# power.net
KiCad netlist of a schematic drawn in Altium Designer
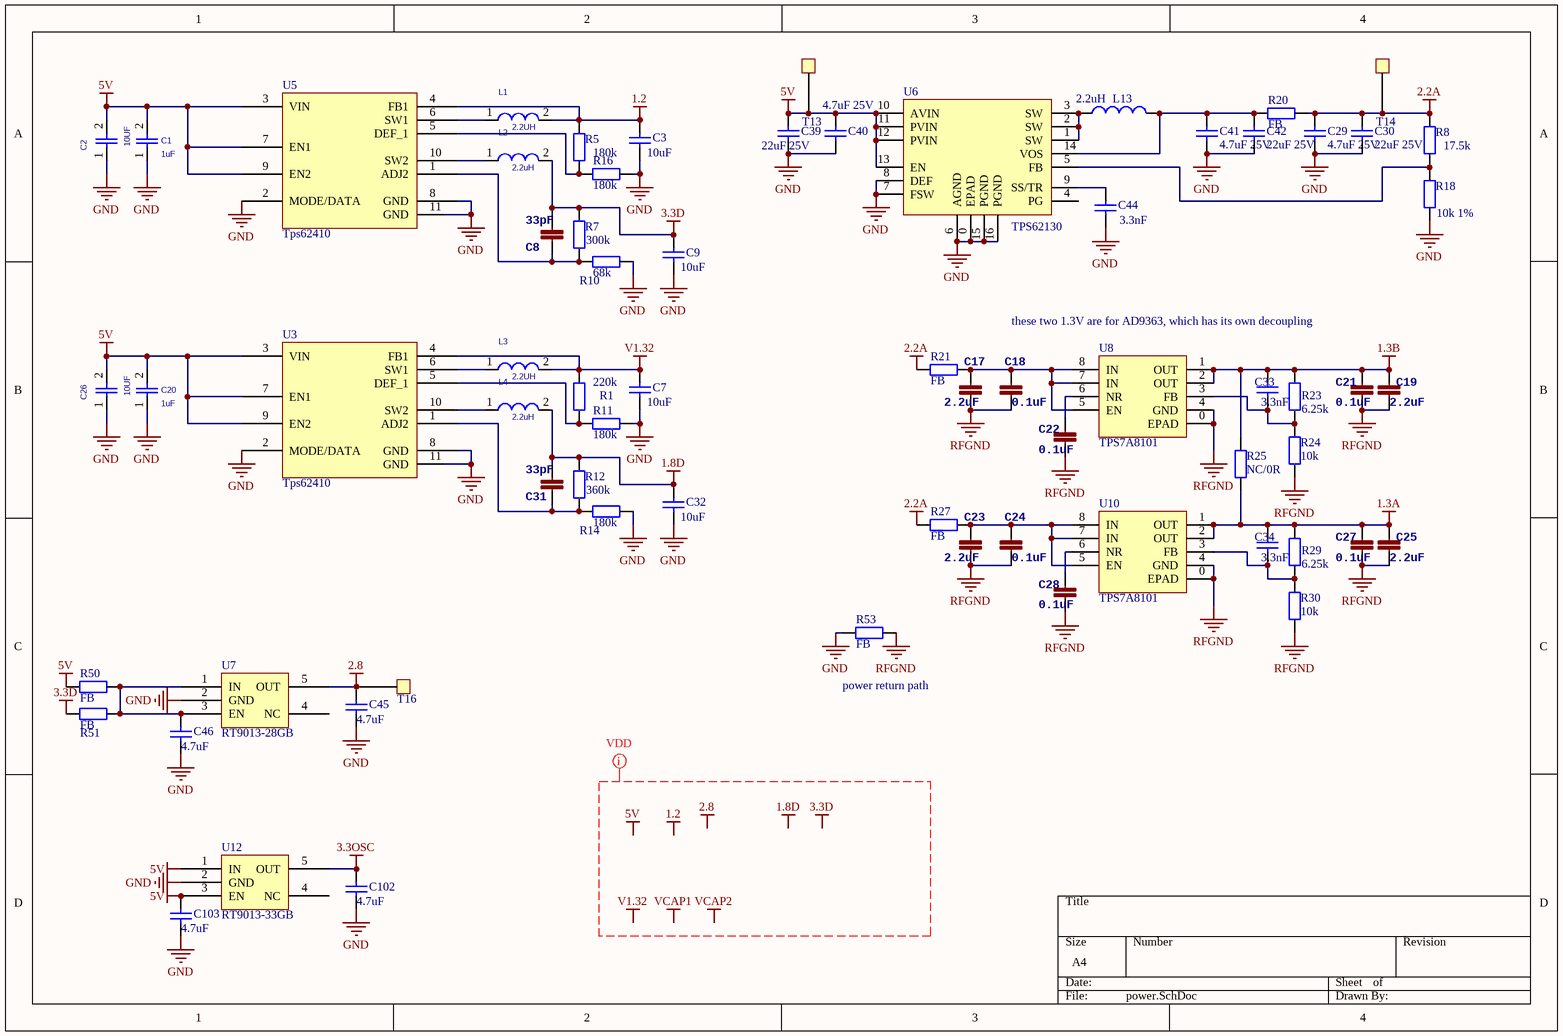
[diagram p0: power.SchDoc]

(export (version "E")
  (design (tool "Eeschema 10.0.6"))
  (components
    (comp (ref "C1") (value "1uF") (footprint "0603") (libsource (lib "*") (part "CAP/0402")))
    (comp (ref "C2") (value "10UF") (footprint "0805") (libsource (lib "*") (part "CAP/0402")))
    (comp (ref "C3")
      (value "10uF")
      (footprint "0805")
      (description "Capacitor")
      (fields (field (name "PUBLISHER") "Altium Limited"))
      (libsource (lib "RTC6705") (part "Cap"))
    )
    (comp (ref "C7")
      (value "10uF")
      (footprint "0805")
      (description "Capacitor")
      (fields (field (name "PUBLISHER") "Altium Limited"))
      (libsource (lib "RTC6705") (part "Cap"))
    )
    (comp (ref "C8")
      (value "33pF")
      (footprint "0402")
      (description "<b>Capacitor</b>\nStandard 0603 ceramic capacitor, and 0.1\" leaded capacitor.")
      (fields (field (name "PARTNO") "CC0402ZRY5V7BB104"))
      (libsource (lib "") (part "CAP0402-CAP_1"))
    )
    (comp (ref "C9")
      (value "10uF")
      (footprint "0805")
      (description "Capacitor")
      (fields (field (name "PUBLISHER") "Altium Limited"))
      (libsource (lib "RTC6705") (part "Cap"))
    )
    (comp (ref "C17")
      (value "2.2uF")
      (footprint "0603")
      (description "<b>Capacitor</b>\nStandard 0603 ceramic capacitor, and 0.1\" leaded capacitor.")
      (fields (field (name "PARTNO") "CC0402ZRY5V7BB104"))
      (libsource (lib "pixhawk2") (part "CAP0402-CAP"))
    )
    (comp (ref "C18")
      (value "0.1uF")
      (footprint "0402")
      (description "<b>Capacitor</b>\nStandard 0603 ceramic capacitor, and 0.1\" leaded capacitor.")
      (fields (field (name "PARTNO") "CC0402ZRY5V7BB104"))
      (libsource (lib "*") (part "CAP0402-CAP"))
    )
    (comp (ref "C19")
      (value "2.2uF")
      (footprint "0603")
      (description "<b>Capacitor</b>\nStandard 0603 ceramic capacitor, and 0.1\" leaded capacitor.")
      (fields (field (name "PARTNO") "CC0402ZRY5V7BB104"))
      (libsource (lib "pixhawk2") (part "CAP0402-CAP"))
    )
    (comp (ref "C20") (value "1uF") (footprint "0603") (libsource (lib "*") (part "CAP/0402")))
    (comp (ref "C21")
      (value "0.1uF")
      (footprint "0603")
      (description "<b>Capacitor</b>\nStandard 0603 ceramic capacitor, and 0.1\" leaded capacitor.")
      (fields (field (name "PARTNO") "CC0402ZRY5V7BB104"))
      (libsource (lib "*") (part "CAP0402-CAP"))
    )
    (comp (ref "C22")
      (value "0.1uF")
      (footprint "0402")
      (description "<b>Capacitor</b>\nStandard 0603 ceramic capacitor, and 0.1\" leaded capacitor.")
      (fields (field (name "PARTNO") "CC0402ZRY5V7BB104"))
      (libsource (lib "*") (part "CAP0402-CAP"))
    )
    (comp (ref "C23")
      (value "2.2uF")
      (footprint "0603")
      (description "<b>Capacitor</b>\nStandard 0603 ceramic capacitor, and 0.1\" leaded capacitor.")
      (fields (field (name "PARTNO") "CC0402ZRY5V7BB104"))
      (libsource (lib "pixhawk2") (part "CAP0402-CAP"))
    )
    (comp (ref "C24")
      (value "0.1uF")
      (footprint "0402")
      (description "<b>Capacitor</b>\nStandard 0603 ceramic capacitor, and 0.1\" leaded capacitor.")
      (fields (field (name "PARTNO") "CC0402ZRY5V7BB104"))
      (libsource (lib "*") (part "CAP0402-CAP"))
    )
    (comp (ref "C25")
      (value "2.2uF")
      (footprint "0603")
      (description "<b>Capacitor</b>\nStandard 0603 ceramic capacitor, and 0.1\" leaded capacitor.")
      (fields (field (name "PARTNO") "CC0402ZRY5V7BB104"))
      (libsource (lib "pixhawk2") (part "CAP0402-CAP"))
    )
    (comp (ref "C26") (value "10UF") (footprint "0805") (libsource (lib "*") (part "CAP/0402")))
    (comp (ref "C27")
      (value "0.1uF")
      (footprint "0603")
      (description "<b>Capacitor</b>\nStandard 0603 ceramic capacitor, and 0.1\" leaded capacitor.")
      (fields (field (name "PARTNO") "CC0402ZRY5V7BB104"))
      (libsource (lib "*") (part "CAP0402-CAP"))
    )
    (comp (ref "C28")
      (value "0.1uF")
      (footprint "0402")
      (description "<b>Capacitor</b>\nStandard 0603 ceramic capacitor, and 0.1\" leaded capacitor.")
      (fields (field (name "PARTNO") "CC0402ZRY5V7BB104"))
      (libsource (lib "*") (part "CAP0402-CAP"))
    )
    (comp (ref "C29")
      (value "4.7uF 25V")
      (footprint "0603")
      (description "Capacitor")
      (fields (field (name "Comment") "Cap") (field (name "PUBLISHER") "Altium Limited"))
      (libsource (lib "RTC6705") (part "Cap"))
    )
    (comp (ref "C30")
      (value "22uF 25V")
      (footprint "0805")
      (description "Capacitor")
      (fields (field (name "Comment") "Cap") (field (name "PUBLISHER") "Altium Limited"))
      (libsource (lib "RTC6705") (part "Cap"))
    )
    (comp (ref "C31")
      (value "33pF")
      (footprint "0402")
      (description "<b>Capacitor</b>\nStandard 0603 ceramic capacitor, and 0.1\" leaded capacitor.")
      (fields (field (name "PARTNO") "CC0402ZRY5V7BB104"))
      (libsource (lib "") (part "CAP0402-CAP_1"))
    )
    (comp (ref "C32")
      (value "10uF")
      (footprint "0805")
      (description "Capacitor")
      (fields (field (name "PUBLISHER") "Altium Limited"))
      (libsource (lib "RTC6705") (part "Cap"))
    )
    (comp (ref "C33")
      (value "3.3nF")
      (footprint "0402")
      (description "Capacitor")
      (fields (field (name "PUBLISHER") "Altium Limited"))
      (libsource (lib "RTC6705") (part "Cap"))
    )
    (comp (ref "C34")
      (value "3.3nF")
      (footprint "0402")
      (description "Capacitor")
      (fields (field (name "PUBLISHER") "Altium Limited"))
      (libsource (lib "RTC6705") (part "Cap"))
    )
    (comp (ref "C39")
      (value "22uF 25V")
      (footprint "0805")
      (description "Capacitor")
      (fields (field (name "Comment") "Cap") (field (name "PUBLISHER") "Altium Limited"))
      (libsource (lib "RTC6705") (part "Cap"))
    )
    (comp (ref "C40")
      (value "4.7uF 25V")
      (footprint "0603")
      (description "Capacitor")
      (fields (field (name "Comment") "Cap") (field (name "PUBLISHER") "Altium Limited"))
      (libsource (lib "RTC6705") (part "Cap"))
    )
    (comp (ref "C41")
      (value "4.7uF 25V")
      (footprint "0603")
      (description "Capacitor")
      (fields (field (name "Comment") "Cap") (field (name "PUBLISHER") "Altium Limited"))
      (libsource (lib "RTC6705") (part "Cap"))
    )
    (comp (ref "C42")
      (value "22uF 25V")
      (footprint "0805")
      (description "Capacitor")
      (fields (field (name "Comment") "Cap") (field (name "PUBLISHER") "Altium Limited"))
      (libsource (lib "RTC6705") (part "Cap"))
    )
    (comp (ref "C44")
      (value "3.3nF")
      (footprint "0402")
      (description "Capacitor")
      (fields (field (name "PUBLISHER") "Altium Limited"))
      (libsource (lib "RTC6705") (part "Cap"))
    )
    (comp (ref "C45")
      (value "4.7uF")
      (footprint "0603")
      (description "Capacitor")
      (fields (field (name "PUBLISHER") "Altium Limited"))
      (libsource (lib "RTC6705") (part "Cap"))
    )
    (comp (ref "C46")
      (value "4.7uF")
      (footprint "0603")
      (description "Capacitor")
      (fields (field (name "PUBLISHER") "Altium Limited"))
      (libsource (lib "RTC6705") (part "Cap"))
    )
    (comp (ref "C102")
      (value "4.7uF")
      (footprint "0603")
      (description "Capacitor")
      (fields (field (name "PUBLISHER") "Altium Limited"))
      (libsource (lib "RTC6705") (part "Cap"))
    )
    (comp (ref "C103")
      (value "4.7uF")
      (footprint "0603")
      (description "Capacitor")
      (fields (field (name "PUBLISHER") "Altium Limited"))
      (libsource (lib "RTC6705") (part "Cap"))
    )
    (comp (ref "L1") (value "2.2UH") (footprint "0806") (libsource (lib "*") (part "L/2.5*2.0")))
    (comp (ref "L2") (value "2.2uH") (footprint "0806") (libsource (lib "*") (part "L/2.5*2.0")))
    (comp (ref "L3") (value "2.2UH") (footprint "0806") (libsource (lib "*") (part "L/2.5*2.0")))
    (comp (ref "L4") (value "2.2uH") (footprint "0806") (libsource (lib "*") (part "L/2.5*2.0")))
    (comp (ref "L13")
      (value "2.2uH")
      (footprint "L3015")
      (description "Inductor")
      (fields (field (name "PUBLISHER") "Altium Limited"))
      (libsource (lib "Miscellaneous Devices") (part "Inductor"))
    )
    (comp (ref "R1")
      (value "220k")
      (footprint "0402")
      (description "Resistor")
      (fields (field (name "PUBLISHER") "Altium Limited"))
      (libsource (lib "RTC6705") (part "Res2"))
    )
    (comp (ref "R5")
      (value "180k")
      (footprint "0402")
      (description "Resistor")
      (fields (field (name "PUBLISHER") "Altium Limited"))
      (libsource (lib "RTC6705") (part "Res2"))
    )
    (comp (ref "R7")
      (value "300k")
      (footprint "0402")
      (description "Resistor")
      (fields (field (name "PUBLISHER") "Altium Limited"))
      (libsource (lib "RTC6705") (part "Res2"))
    )
    (comp (ref "R8")
      (value "17.5k")
      (footprint "0402")
      (description "Resistor")
      (fields (field (name "PUBLISHER") "Altium Limited"))
      (libsource (lib "RTC6705") (part "Res2"))
    )
    (comp (ref "R10")
      (value "68k")
      (footprint "0402")
      (description "Resistor")
      (fields (field (name "PUBLISHER") "Altium Limited"))
      (libsource (lib "") (part "Res2_1"))
    )
    (comp (ref "R11")
      (value "180k")
      (footprint "0402")
      (description "Resistor")
      (fields (field (name "PUBLISHER") "Altium Limited"))
      (libsource (lib "") (part "Res2_1"))
    )
    (comp (ref "R12")
      (value "360k")
      (footprint "0402")
      (description "Resistor")
      (fields (field (name "PUBLISHER") "Altium Limited"))
      (libsource (lib "RTC6705") (part "Res2"))
    )
    (comp (ref "R14")
      (value "180k")
      (footprint "0402")
      (description "Resistor")
      (fields (field (name "PUBLISHER") "Altium Limited"))
      (libsource (lib "") (part "Res2_1"))
    )
    (comp (ref "R16")
      (value "180k")
      (footprint "0402")
      (description "Resistor")
      (fields (field (name "PUBLISHER") "Altium Limited"))
      (libsource (lib "") (part "Res2_1"))
    )
    (comp (ref "R18")
      (value "10k 1%")
      (footprint "0402")
      (description "Resistor")
      (fields (field (name "PUBLISHER") "Altium Limited"))
      (libsource (lib "RTC6705") (part "Res2"))
    )
    (comp (ref "R20")
      (value "FB")
      (footprint "0603")
      (description "Resistor")
      (fields (field (name "PUBLISHER") "Altium Limited"))
      (libsource (lib "Miscellaneous Devices") (part "Res2"))
    )
    (comp (ref "R21")
      (value "FB")
      (footprint "0603")
      (description "Resistor")
      (fields (field (name "PUBLISHER") "Altium Limited"))
      (libsource (lib "Miscellaneous Devices") (part "Res2"))
    )
    (comp (ref "R23")
      (value "6.25k")
      (footprint "0402")
      (description "Resistor")
      (fields (field (name "PUBLISHER") "Altium Limited"))
      (libsource (lib "") (part "Res2_2"))
    )
    (comp (ref "R24")
      (value "10k")
      (footprint "0402")
      (description "Resistor")
      (fields (field (name "PUBLISHER") "Altium Limited"))
      (libsource (lib "") (part "Res2_2"))
    )
    (comp (ref "R25")
      (value "NC/0R")
      (footprint "0603")
      (description "Resistor")
      (fields (field (name "PUBLISHER") "Altium Limited"))
      (libsource (lib "") (part "Res2_2"))
    )
    (comp (ref "R27")
      (value "FB")
      (footprint "0603")
      (description "Resistor")
      (fields (field (name "PUBLISHER") "Altium Limited"))
      (libsource (lib "Miscellaneous Devices") (part "Res2"))
    )
    (comp (ref "R29")
      (value "6.25k")
      (footprint "0402")
      (description "Resistor")
      (fields (field (name "PUBLISHER") "Altium Limited"))
      (libsource (lib "") (part "Res2_2"))
    )
    (comp (ref "R30")
      (value "10k")
      (footprint "0402")
      (description "Resistor")
      (fields (field (name "PUBLISHER") "Altium Limited"))
      (libsource (lib "") (part "Res2_2"))
    )
    (comp (ref "R50")
      (value "FB")
      (footprint "0603")
      (description "Resistor")
      (fields (field (name "PUBLISHER") "Altium Limited"))
      (libsource (lib "") (part "Res2_1"))
    )
    (comp (ref "R51")
      (value "FB")
      (footprint "0603")
      (description "Resistor")
      (fields (field (name "PUBLISHER") "Altium Limited"))
      (libsource (lib "") (part "Res2_1"))
    )
    (comp (ref "R53")
      (value "FB")
      (footprint "0603")
      (description "Resistor")
      (fields (field (name "PUBLISHER") "Altium Limited"))
      (libsource (lib "Miscellaneous Devices") (part "Res2"))
    )
    (comp (ref "T13") (value "TestPad") (footprint "TestPad - 1mm") (libsource (lib "") (part "TestPad_1")))
    (comp (ref "T14") (value "TestPad") (footprint "TestPad - 1mm") (libsource (lib "") (part "TestPad_1")))
    (comp (ref "T16") (value "TestPad") (footprint "TestPad - 1mm") (libsource (lib "sch") (part "TestPad")))
    (comp (ref "U3") (value "Tps62410") (footprint "DFN-10P-3X3") (libsource (lib "Euler") (part "Tps62410")))
    (comp (ref "U5") (value "Tps62410") (footprint "DFN-10P-3X3") (libsource (lib "Euler") (part "Tps62410")))
    (comp (ref "U6") (value "TPS62130") (footprint "TPS62130") (libsource (lib "sch") (part "TPS62130")))
    (comp (ref "U7") (value "RT9013-28GB") (footprint "SOT23-5") (libsource (lib "RTC6705") (part "LP5907")))
    (comp (ref "U8") (value "TPS7A8101") (footprint "TPS7A8101") (libsource (lib "F4SDR") (part "TPS7A8101")))
    (comp (ref "U10")
      (value "TPS7A8101")
      (footprint "TPS7A8101")
      (libsource (lib "F4SDR") (part "TPS7A8101"))
    )
    (comp (ref "U12") (value "RT9013-33GB") (footprint "SOT23-5") (libsource (lib "RTC6705") (part "LP5907")))
  )
  (nets
    (net (code "1") (name "1.2") (class "Default")
      (node (ref "C3") (pin "2") (pinfunction "2_2") (pintype "passive"))
      (node (ref "L1") (pin "2") (pinfunction "2_2") (pintype "passive"))
      (node (ref "R5") (pin "1") (pinfunction "1_1") (pintype "passive"))
      (node (ref "U5") (pin "4") (pinfunction "FB1_4") (pintype "passive"))
    )
    (net (code "2") (name "1.3A") (class "Default")
      (node (ref "C25") (pin "2") (pinfunction "2_2") (pintype "passive"))
      (node (ref "C27") (pin "2") (pinfunction "2_2") (pintype "passive"))
      (node (ref "C34") (pin "1") (pinfunction "1_1") (pintype "passive"))
      (node (ref "R25") (pin "2") (pinfunction "2_2") (pintype "passive"))
      (node (ref "R29") (pin "1") (pinfunction "1_1") (pintype "passive"))
      (node (ref "U10") (pin "1") (pinfunction "OUT_1") (pintype "passive"))
      (node (ref "U10") (pin "2") (pinfunction "OUT_2") (pintype "passive"))
    )
    (net (code "3") (name "1.3B") (class "Default")
      (node (ref "C19") (pin "2") (pinfunction "2_2") (pintype "passive"))
      (node (ref "C21") (pin "2") (pinfunction "2_2") (pintype "passive"))
      (node (ref "C33") (pin "1") (pinfunction "1_1") (pintype "passive"))
      (node (ref "R23") (pin "1") (pinfunction "1_1") (pintype "passive"))
      (node (ref "R25") (pin "1") (pinfunction "1_1") (pintype "passive"))
      (node (ref "U8") (pin "1") (pinfunction "OUT_1") (pintype "passive"))
      (node (ref "U8") (pin "2") (pinfunction "OUT_2") (pintype "passive"))
    )
    (net (code "4") (name "1.8D") (class "Default")
      (node (ref "C31") (pin "1") (pinfunction "1_1") (pintype "passive"))
      (node (ref "C32") (pin "2") (pinfunction "2_2") (pintype "passive"))
      (node (ref "L4") (pin "2") (pinfunction "2_2") (pintype "passive"))
      (node (ref "R12") (pin "1") (pinfunction "1_1") (pintype "passive"))
    )
    (net (code "5") (name "2.2A") (class "Default")
      (node (ref "C29") (pin "2") (pinfunction "2_2") (pintype "passive"))
      (node (ref "C30") (pin "2") (pinfunction "2_2") (pintype "passive"))
      (node (ref "R20") (pin "1") (pinfunction "1_1") (pintype "passive"))
      (node (ref "R21") (pin "2") (pinfunction "2_2") (pintype "passive"))
      (node (ref "R27") (pin "2") (pinfunction "2_2") (pintype "passive"))
      (node (ref "R8") (pin "1") (pinfunction "1_1") (pintype "passive"))
      (node (ref "T14") (pin "1") (pinfunction "3_1") (pintype "passive"))
    )
    (net (code "6") (name "2.8") (class "Default")
      (node (ref "C45") (pin "2") (pinfunction "2_2") (pintype "passive"))
      (node (ref "T16") (pin "1") (pinfunction "3_1") (pintype "passive"))
      (node (ref "U7") (pin "5") (pinfunction "OUT_5") (pintype "passive"))
    )
    (net (code "7") (name "3.3D") (class "Default")
      (node (ref "C8") (pin "1") (pinfunction "1_1") (pintype "passive"))
      (node (ref "C9") (pin "2") (pinfunction "2_2") (pintype "passive"))
      (node (ref "L2") (pin "2") (pinfunction "2_2") (pintype "passive"))
      (node (ref "R51") (pin "1") (pinfunction "1_1") (pintype "passive"))
      (node (ref "R7") (pin "1") (pinfunction "1_1") (pintype "passive"))
    )
    (net (code "8") (name "3.3OSC") (class "Default")
      (node (ref "C102") (pin "2") (pinfunction "2_2") (pintype "passive"))
      (node (ref "U12") (pin "5") (pinfunction "OUT_5") (pintype "passive"))
    )
    (net (code "9") (name "5V") (class "Default")
      (node (ref "C1") (pin "2") (pinfunction "2_2") (pintype "passive"))
      (node (ref "C103") (pin "2") (pinfunction "2_2") (pintype "passive"))
      (node (ref "C2") (pin "2") (pinfunction "2_2") (pintype "passive"))
      (node (ref "C20") (pin "2") (pinfunction "2_2") (pintype "passive"))
      (node (ref "C26") (pin "2") (pinfunction "2_2") (pintype "passive"))
      (node (ref "C39") (pin "1") (pinfunction "1_1") (pintype "passive"))
      (node (ref "C40") (pin "1") (pinfunction "1_1") (pintype "passive"))
      (node (ref "R50") (pin "1") (pinfunction "1_1") (pintype "passive"))
      (node (ref "T13") (pin "1") (pinfunction "3_1") (pintype "passive"))
      (node (ref "U12") (pin "1") (pinfunction "IN_1") (pintype "passive"))
      (node (ref "U12") (pin "3") (pinfunction "EN_3") (pintype "passive"))
      (node (ref "U3") (pin "3") (pinfunction "VIN_3") (pintype "passive"))
      (node (ref "U3") (pin "7") (pinfunction "EN1_7") (pintype "passive"))
      (node (ref "U3") (pin "9") (pinfunction "EN2_9") (pintype "passive"))
      (node (ref "U5") (pin "3") (pinfunction "VIN_3") (pintype "passive"))
      (node (ref "U5") (pin "7") (pinfunction "EN1_7") (pintype "passive"))
      (node (ref "U5") (pin "9") (pinfunction "EN2_9") (pintype "passive"))
      (node (ref "U6") (pin "10") (pinfunction "AVIN_10") (pintype "passive"))
      (node (ref "U6") (pin "11") (pinfunction "PVIN_11") (pintype "passive"))
      (node (ref "U6") (pin "12") (pinfunction "PVIN_12") (pintype "passive"))
      (node (ref "U6") (pin "13") (pinfunction "EN_13") (pintype "passive"))
    )
    (net (code "10") (name "GND") (class "Default")
      (node (ref "C1") (pin "1") (pinfunction "1_1") (pintype "passive"))
      (node (ref "C102") (pin "1") (pinfunction "1_1") (pintype "passive"))
      (node (ref "C103") (pin "1") (pinfunction "1_1") (pintype "passive"))
      (node (ref "C2") (pin "1") (pinfunction "1_1") (pintype "passive"))
      (node (ref "C20") (pin "1") (pinfunction "1_1") (pintype "passive"))
      (node (ref "C26") (pin "1") (pinfunction "1_1") (pintype "passive"))
      (node (ref "C29") (pin "1") (pinfunction "1_1") (pintype "passive"))
      (node (ref "C3") (pin "1") (pinfunction "1_1") (pintype "passive"))
      (node (ref "C30") (pin "1") (pinfunction "1_1") (pintype "passive"))
      (node (ref "C32") (pin "1") (pinfunction "1_1") (pintype "passive"))
      (node (ref "C39") (pin "2") (pinfunction "2_2") (pintype "passive"))
      (node (ref "C40") (pin "2") (pinfunction "2_2") (pintype "passive"))
      (node (ref "C41") (pin "1") (pinfunction "1_1") (pintype "passive"))
      (node (ref "C42") (pin "1") (pinfunction "1_1") (pintype "passive"))
      (node (ref "C44") (pin "2") (pinfunction "2_2") (pintype "passive"))
      (node (ref "C45") (pin "1") (pinfunction "1_1") (pintype "passive"))
      (node (ref "C46") (pin "1") (pinfunction "1_1") (pintype "passive"))
      (node (ref "C7") (pin "1") (pinfunction "1_1") (pintype "passive"))
      (node (ref "C9") (pin "1") (pinfunction "1_1") (pintype "passive"))
      (node (ref "R10") (pin "2") (pinfunction "2_2") (pintype "passive"))
      (node (ref "R11") (pin "2") (pinfunction "2_2") (pintype "passive"))
      (node (ref "R14") (pin "2") (pinfunction "2_2") (pintype "passive"))
      (node (ref "R16") (pin "2") (pinfunction "2_2") (pintype "passive"))
      (node (ref "R18") (pin "2") (pinfunction "2_2") (pintype "passive"))
      (node (ref "R53") (pin "2") (pinfunction "2_2") (pintype "passive"))
      (node (ref "U12") (pin "2") (pinfunction "GND_2") (pintype "passive"))
      (node (ref "U3") (pin "11") (pinfunction "GND_11") (pintype "passive"))
      (node (ref "U3") (pin "2") (pinfunction "MODE/DATA_2") (pintype "passive"))
      (node (ref "U3") (pin "8") (pinfunction "GND_8") (pintype "passive"))
      (node (ref "U5") (pin "11") (pinfunction "GND_11") (pintype "passive"))
      (node (ref "U5") (pin "2") (pinfunction "MODE/DATA_2") (pintype "passive"))
      (node (ref "U5") (pin "8") (pinfunction "GND_8") (pintype "passive"))
      (node (ref "U6") (pin "0") (pinfunction "EPAD_0") (pintype "passive"))
      (node (ref "U6") (pin "15") (pinfunction "PGND_15") (pintype "passive"))
      (node (ref "U6") (pin "16") (pinfunction "PGND_16") (pintype "passive"))
      (node (ref "U6") (pin "6") (pinfunction "AGND_6") (pintype "passive"))
      (node (ref "U6") (pin "7") (pinfunction "FSW_7") (pintype "passive"))
      (node (ref "U6") (pin "8") (pinfunction "DEF_8") (pintype "passive"))
      (node (ref "U7") (pin "2") (pinfunction "GND_2") (pintype "passive"))
    )
    (net (code "11") (name "Net-(L13-Pad1)") (class "Default")
      (node (ref "L13") (pin "1") (pinfunction "1_1") (pintype "passive"))
      (node (ref "U6") (pin "1") (pinfunction "SW_1") (pintype "passive"))
      (node (ref "U6") (pin "2") (pinfunction "SW_2") (pintype "passive"))
      (node (ref "U6") (pin "3") (pinfunction "SW_3") (pintype "passive"))
    )
    (net (code "12") (name "Net-(U3-ADJ2)") (class "Default")
      (node (ref "C31") (pin "2") (pinfunction "2_2") (pintype "passive"))
      (node (ref "R12") (pin "2") (pinfunction "2_2") (pintype "passive"))
      (node (ref "R14") (pin "1") (pinfunction "1_1") (pintype "passive"))
      (node (ref "U3") (pin "1") (pinfunction "ADJ2_1") (pintype "passive"))
    )
    (net (code "13") (name "Net-(U3-DEF_1)") (class "Default")
      (node (ref "R1") (pin "2") (pinfunction "2_2") (pintype "passive"))
      (node (ref "R11") (pin "1") (pinfunction "1_1") (pintype "passive"))
      (node (ref "U3") (pin "5") (pinfunction "DEF_1_5") (pintype "passive"))
    )
    (net (code "14") (name "Net-(U3-SW1)") (class "Default")
      (node (ref "L3") (pin "1") (pinfunction "1_1") (pintype "passive"))
      (node (ref "U3") (pin "6") (pinfunction "SW1_6") (pintype "passive"))
    )
    (net (code "15") (name "Net-(U3-SW2)") (class "Default")
      (node (ref "L4") (pin "1") (pinfunction "1_1") (pintype "passive"))
      (node (ref "U3") (pin "10") (pinfunction "SW2_10") (pintype "passive"))
    )
    (net (code "16") (name "Net-(U5-ADJ2)") (class "Default")
      (node (ref "C8") (pin "2") (pinfunction "2_2") (pintype "passive"))
      (node (ref "R10") (pin "1") (pinfunction "1_1") (pintype "passive"))
      (node (ref "R7") (pin "2") (pinfunction "2_2") (pintype "passive"))
      (node (ref "U5") (pin "1") (pinfunction "ADJ2_1") (pintype "passive"))
    )
    (net (code "17") (name "Net-(U5-DEF_1)") (class "Default")
      (node (ref "R16") (pin "1") (pinfunction "1_1") (pintype "passive"))
      (node (ref "R5") (pin "2") (pinfunction "2_2") (pintype "passive"))
      (node (ref "U5") (pin "5") (pinfunction "DEF_1_5") (pintype "passive"))
    )
    (net (code "18") (name "Net-(U5-SW1)") (class "Default")
      (node (ref "L1") (pin "1") (pinfunction "1_1") (pintype "passive"))
      (node (ref "U5") (pin "6") (pinfunction "SW1_6") (pintype "passive"))
    )
    (net (code "19") (name "Net-(U5-SW2)") (class "Default")
      (node (ref "L2") (pin "1") (pinfunction "1_1") (pintype "passive"))
      (node (ref "U5") (pin "10") (pinfunction "SW2_10") (pintype "passive"))
    )
    (net (code "20") (name "Net-(U6-FB)") (class "Default")
      (node (ref "R18") (pin "1") (pinfunction "1_1") (pintype "passive"))
      (node (ref "R8") (pin "2") (pinfunction "2_2") (pintype "passive"))
      (node (ref "U6") (pin "5") (pinfunction "FB_5") (pintype "passive"))
    )
    (net (code "21") (name "Net-(U6-SS{slash}TR)") (class "Default")
      (node (ref "C44") (pin "1") (pinfunction "1_1") (pintype "passive"))
      (node (ref "U6") (pin "9") (pinfunction "SS/TR_9") (pintype "passive"))
    )
    (net (code "22") (name "Net-(U6-VOS)") (class "Default")
      (node (ref "C41") (pin "2") (pinfunction "2_2") (pintype "passive"))
      (node (ref "C42") (pin "2") (pinfunction "2_2") (pintype "passive"))
      (node (ref "L13") (pin "2") (pinfunction "2_2") (pintype "passive"))
      (node (ref "R20") (pin "2") (pinfunction "2_2") (pintype "passive"))
      (node (ref "U6") (pin "14") (pinfunction "VOS_14") (pintype "passive"))
    )
    (net (code "23") (name "Net-(U7-EN)") (class "Default")
      (node (ref "C46") (pin "2") (pinfunction "2_2") (pintype "passive"))
      (node (ref "R50") (pin "2") (pinfunction "2_2") (pintype "passive"))
      (node (ref "R51") (pin "2") (pinfunction "2_2") (pintype "passive"))
      (node (ref "U7") (pin "1") (pinfunction "IN_1") (pintype "passive"))
      (node (ref "U7") (pin "3") (pinfunction "EN_3") (pintype "passive"))
    )
    (net (code "24") (name "Net-(U8-EN)") (class "Default")
      (node (ref "C17") (pin "2") (pinfunction "2_2") (pintype "passive"))
      (node (ref "C18") (pin "2") (pinfunction "2_2") (pintype "passive"))
      (node (ref "R21") (pin "1") (pinfunction "1_1") (pintype "passive"))
      (node (ref "U8") (pin "5") (pinfunction "EN_5") (pintype "passive"))
      (node (ref "U8") (pin "7") (pinfunction "IN_7") (pintype "passive"))
      (node (ref "U8") (pin "8") (pinfunction "IN_8") (pintype "passive"))
    )
    (net (code "25") (name "Net-(U8-FB)") (class "Default")
      (node (ref "C33") (pin "2") (pinfunction "2_2") (pintype "passive"))
      (node (ref "R23") (pin "2") (pinfunction "2_2") (pintype "passive"))
      (node (ref "R24") (pin "1") (pinfunction "1_1") (pintype "passive"))
      (node (ref "U8") (pin "3") (pinfunction "FB_3") (pintype "passive"))
    )
    (net (code "26") (name "Net-(U8-NR)") (class "Default")
      (node (ref "C22") (pin "2") (pinfunction "2_2") (pintype "passive"))
      (node (ref "U8") (pin "6") (pinfunction "NR_6") (pintype "passive"))
    )
    (net (code "27") (name "Net-(U10-EN)") (class "Default")
      (node (ref "C23") (pin "2") (pinfunction "2_2") (pintype "passive"))
      (node (ref "C24") (pin "2") (pinfunction "2_2") (pintype "passive"))
      (node (ref "R27") (pin "1") (pinfunction "1_1") (pintype "passive"))
      (node (ref "U10") (pin "5") (pinfunction "EN_5") (pintype "passive"))
      (node (ref "U10") (pin "7") (pinfunction "IN_7") (pintype "passive"))
      (node (ref "U10") (pin "8") (pinfunction "IN_8") (pintype "passive"))
    )
    (net (code "28") (name "Net-(U10-FB)") (class "Default")
      (node (ref "C34") (pin "2") (pinfunction "2_2") (pintype "passive"))
      (node (ref "R29") (pin "2") (pinfunction "2_2") (pintype "passive"))
      (node (ref "R30") (pin "1") (pinfunction "1_1") (pintype "passive"))
      (node (ref "U10") (pin "3") (pinfunction "FB_3") (pintype "passive"))
    )
    (net (code "29") (name "Net-(U10-NR)") (class "Default")
      (node (ref "C28") (pin "2") (pinfunction "2_2") (pintype "passive"))
      (node (ref "U10") (pin "6") (pinfunction "NR_6") (pintype "passive"))
    )
    (net (code "30") (name "RFGND") (class "Default")
      (node (ref "C17") (pin "1") (pinfunction "1_1") (pintype "passive"))
      (node (ref "C18") (pin "1") (pinfunction "1_1") (pintype "passive"))
      (node (ref "C19") (pin "1") (pinfunction "1_1") (pintype "passive"))
      (node (ref "C21") (pin "1") (pinfunction "1_1") (pintype "passive"))
      (node (ref "C22") (pin "1") (pinfunction "1_1") (pintype "passive"))
      (node (ref "C23") (pin "1") (pinfunction "1_1") (pintype "passive"))
      (node (ref "C24") (pin "1") (pinfunction "1_1") (pintype "passive"))
      (node (ref "C25") (pin "1") (pinfunction "1_1") (pintype "passive"))
      (node (ref "C27") (pin "1") (pinfunction "1_1") (pintype "passive"))
      (node (ref "C28") (pin "1") (pinfunction "1_1") (pintype "passive"))
      (node (ref "R24") (pin "2") (pinfunction "2_2") (pintype "passive"))
      (node (ref "R30") (pin "2") (pinfunction "2_2") (pintype "passive"))
      (node (ref "R53") (pin "1") (pinfunction "1_1") (pintype "passive"))
      (node (ref "U10") (pin "0") (pinfunction "EPAD_0") (pintype "passive"))
      (node (ref "U10") (pin "4") (pinfunction "GND_4") (pintype "passive"))
      (node (ref "U8") (pin "0") (pinfunction "EPAD_0") (pintype "passive"))
      (node (ref "U8") (pin "4") (pinfunction "GND_4") (pintype "passive"))
    )
    (net (code "31") (name "V1.32") (class "Default")
      (node (ref "C7") (pin "2") (pinfunction "2_2") (pintype "passive"))
      (node (ref "L3") (pin "2") (pinfunction "2_2") (pintype "passive"))
      (node (ref "R1") (pin "1") (pinfunction "1_1") (pintype "passive"))
      (node (ref "U3") (pin "4") (pinfunction "FB1_4") (pintype "passive"))
    )
    (net (code "34") (name "unconnected-(U6-PG-Pad4)") (class "Default")
      (node (ref "U6") (pin "4") (pinfunction "PG_4") (pintype "passive"))
    )
    (net (code "35") (name "unconnected-(U7-NC-Pad4)") (class "Default")
      (node (ref "U7") (pin "4") (pinfunction "NC_4") (pintype "passive"))
    )
    (net (code "36") (name "unconnected-(U12-NC-Pad4)") (class "Default")
      (node (ref "U12") (pin "4") (pinfunction "NC_4") (pintype "passive"))
    )
  )
)
